# MBO.net
KiCad netlist of a schematic drawn in EAGLE
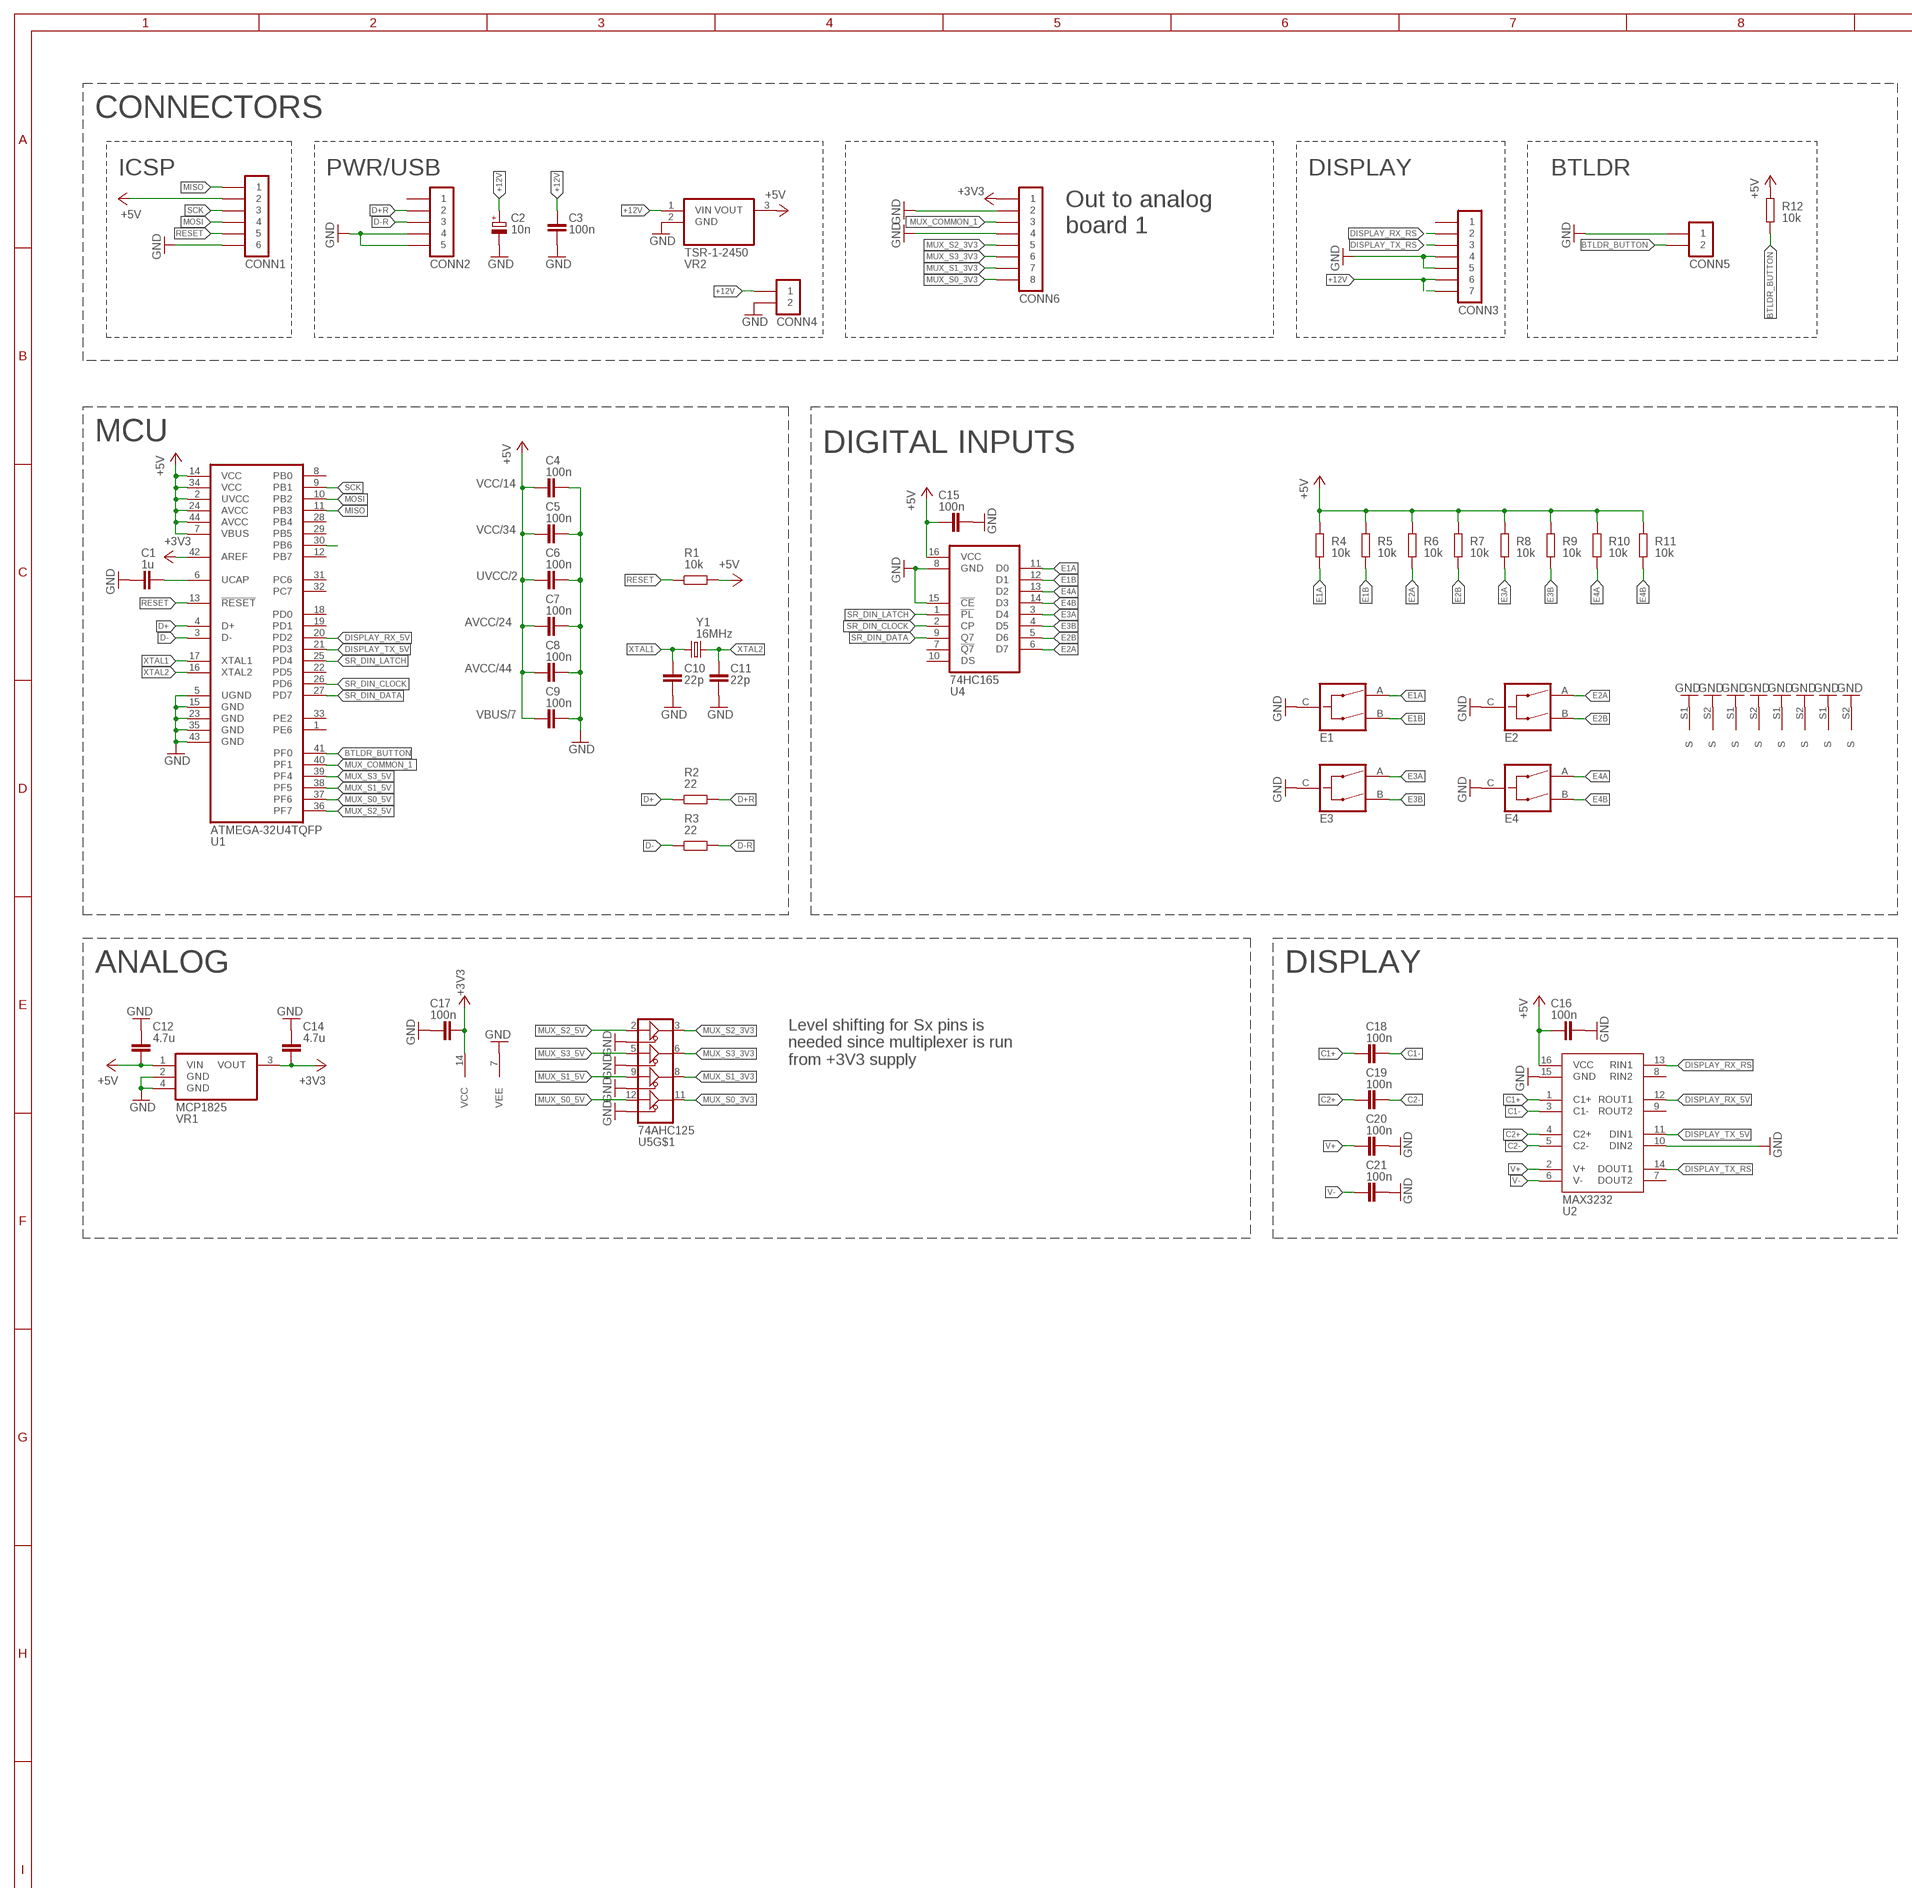
[diagram p0: schematic, sheet 1, part 1 of 2]
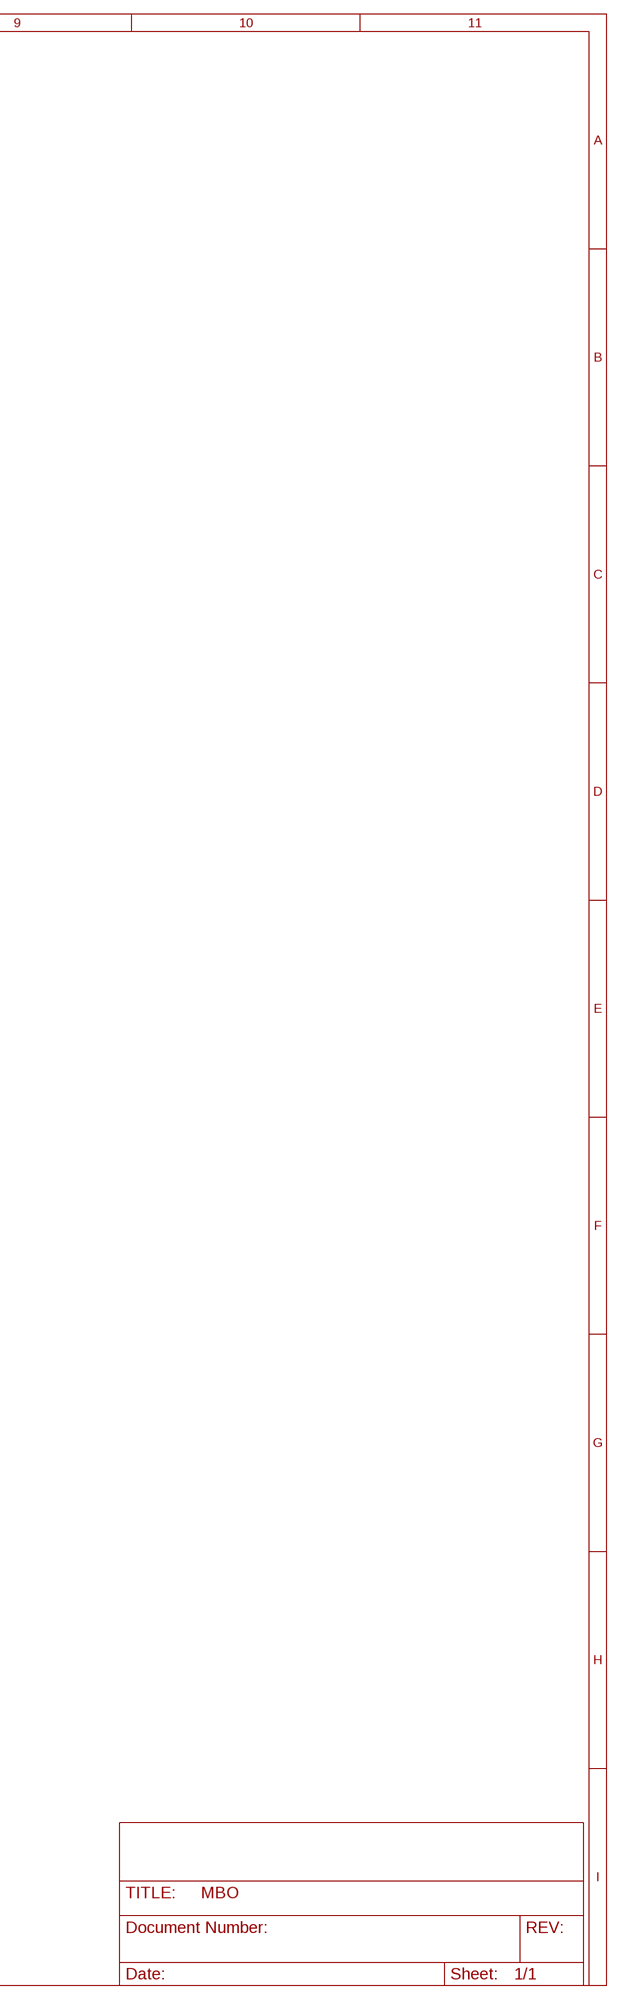
[diagram p1: schematic, sheet 1, part 2 of 2]

(export (version "E")
  (design (tool "Eeschema 10.0.6"))
  (components
    (comp (ref "C1")
      (value "1u")
      (footprint "eagle-import:C0805")
      (libsource (lib "eagle-import") (part "CAPACITOR-0805"))
    )
    (comp (ref "C2")
      (value "10n")
      (footprint "eagle-import:153CLV-0405")
      (fields (field (name "MANUFACTURER") "Multicomp") (field (name "MPN") "MCVVT016M100CA1L"))
      (libsource (lib "eagle-import") (part "ELECTROLYTIC_CAPACITOR-CLV-040516V"))
    )
    (comp (ref "C3")
      (value "100n")
      (footprint "eagle-import:C0805")
      (libsource (lib "eagle-import") (part "CAPACITOR-0805"))
    )
    (comp (ref "C4")
      (value "100n")
      (footprint "eagle-import:C0805")
      (libsource (lib "eagle-import") (part "CAPACITOR-0805"))
    )
    (comp (ref "C5")
      (value "100n")
      (footprint "eagle-import:C0805")
      (libsource (lib "eagle-import") (part "CAPACITOR-0805"))
    )
    (comp (ref "C6")
      (value "100n")
      (footprint "eagle-import:C0805")
      (libsource (lib "eagle-import") (part "CAPACITOR-0805"))
    )
    (comp (ref "C7")
      (value "100n")
      (footprint "eagle-import:C0805")
      (libsource (lib "eagle-import") (part "CAPACITOR-0805"))
    )
    (comp (ref "C8")
      (value "100n")
      (footprint "eagle-import:C0805")
      (libsource (lib "eagle-import") (part "CAPACITOR-0805"))
    )
    (comp (ref "C9")
      (value "100n")
      (footprint "eagle-import:C0805")
      (libsource (lib "eagle-import") (part "CAPACITOR-0805"))
    )
    (comp (ref "C10")
      (value "22p")
      (footprint "eagle-import:C0805")
      (libsource (lib "eagle-import") (part "CAPACITOR-0805"))
    )
    (comp (ref "C11")
      (value "22p")
      (footprint "eagle-import:C0805")
      (libsource (lib "eagle-import") (part "CAPACITOR-0805"))
    )
    (comp (ref "C12")
      (value "4.7u")
      (footprint "eagle-import:C0805")
      (libsource (lib "eagle-import") (part "CAPACITOR-0805"))
    )
    (comp (ref "C14")
      (value "4.7u")
      (footprint "eagle-import:C0805")
      (libsource (lib "eagle-import") (part "CAPACITOR-0805"))
    )
    (comp (ref "C15")
      (value "100n")
      (footprint "eagle-import:C0805")
      (libsource (lib "eagle-import") (part "CAPACITOR-0805"))
    )
    (comp (ref "C16")
      (value "100n")
      (footprint "eagle-import:C0805")
      (libsource (lib "eagle-import") (part "CAPACITOR-0805"))
    )
    (comp (ref "C17")
      (value "100n")
      (footprint "eagle-import:C0805")
      (libsource (lib "eagle-import") (part "CAPACITOR-0805"))
    )
    (comp (ref "C18")
      (value "100n")
      (footprint "eagle-import:C0805")
      (libsource (lib "eagle-import") (part "CAPACITOR-0805"))
    )
    (comp (ref "C19")
      (value "100n")
      (footprint "eagle-import:C0805")
      (libsource (lib "eagle-import") (part "CAPACITOR-0805"))
    )
    (comp (ref "C20")
      (value "100n")
      (footprint "eagle-import:C0805")
      (libsource (lib "eagle-import") (part "CAPACITOR-0805"))
    )
    (comp (ref "C21")
      (value "100n")
      (footprint "eagle-import:C0805")
      (libsource (lib "eagle-import") (part "CAPACITOR-0805"))
    )
    (comp (ref "CONN1")
      (value "PINHD-2X03-TH-2.54MM-V")
      (footprint "eagle-import:2X03-2.54-V")
      (libsource (lib "eagle-import") (part "PINHD-2X03-TH-2.54MM-V"))
    )
    (comp (ref "CONN2")
      (value "PINHD-1X05-JST-XH-H")
      (footprint "eagle-import:JST-XH-05P-H")
      (libsource (lib "eagle-import") (part "PINHD-1X05-JST-XH-H"))
    )
    (comp (ref "CONN3")
      (value "PINHD-1X07-JST-H")
      (footprint "eagle-import:JST-XH-07P-H")
      (libsource (lib "eagle-import") (part "PINHD-1X07-JST-H"))
    )
    (comp (ref "CONN4")
      (value "PINHD-1X02-MOLEX-39357-0002")
      (footprint "eagle-import:MOLEX-39357-0002")
      (fields (field (name "MANUFACTURER") "Molex") (field (name "MPN") "39357-0002"))
      (libsource (lib "eagle-import") (part "PINHD-1X02-MOLEX-39357-0002"))
    )
    (comp (ref "CONN5")
      (value "PINHD-1X02-JST-XH-H")
      (footprint "eagle-import:JST-XH-02P-H")
      (libsource (lib "eagle-import") (part "PINHD-1X02-JST-XH-H"))
    )
    (comp (ref "CONN6")
      (value "PINHD-2X04-IDC-2.54-V")
      (footprint "eagle-import:IDC-08P-2.54")
      (libsource (lib "eagle-import") (part "PINHD-2X04-IDC-2.54-V"))
    )
    (comp (ref "E1")
      (value "ALPS-EC12E24404AX")
      (footprint "eagle-import:EC12E-1")
      (libsource (lib "eagle-import") (part "ALPS-EC12E24404AX"))
    )
    (comp (ref "E2")
      (value "ALPS-EC12E24404AX")
      (footprint "eagle-import:EC12E-1")
      (libsource (lib "eagle-import") (part "ALPS-EC12E24404AX"))
    )
    (comp (ref "E3")
      (value "ALPS-EC12E24404AX")
      (footprint "eagle-import:EC12E-1")
      (libsource (lib "eagle-import") (part "ALPS-EC12E24404AX"))
    )
    (comp (ref "E4")
      (value "ALPS-EC12E24404AX")
      (footprint "eagle-import:EC12E-1")
      (libsource (lib "eagle-import") (part "ALPS-EC12E24404AX"))
    )
    (comp (ref "R1")
      (value "10k")
      (footprint "eagle-import:R0805")
      (libsource (lib "eagle-import") (part "RESISTOR-0805"))
    )
    (comp (ref "R2")
      (value "22")
      (footprint "eagle-import:R0805")
      (libsource (lib "eagle-import") (part "RESISTOR-0805"))
    )
    (comp (ref "R3")
      (value "22")
      (footprint "eagle-import:R0805")
      (libsource (lib "eagle-import") (part "RESISTOR-0805"))
    )
    (comp (ref "R4")
      (value "10k")
      (footprint "eagle-import:R0805")
      (libsource (lib "eagle-import") (part "RESISTOR-0805"))
    )
    (comp (ref "R5")
      (value "10k")
      (footprint "eagle-import:R0805")
      (libsource (lib "eagle-import") (part "RESISTOR-0805"))
    )
    (comp (ref "R6")
      (value "10k")
      (footprint "eagle-import:R0805")
      (libsource (lib "eagle-import") (part "RESISTOR-0805"))
    )
    (comp (ref "R7")
      (value "10k")
      (footprint "eagle-import:R0805")
      (libsource (lib "eagle-import") (part "RESISTOR-0805"))
    )
    (comp (ref "R8")
      (value "10k")
      (footprint "eagle-import:R0805")
      (libsource (lib "eagle-import") (part "RESISTOR-0805"))
    )
    (comp (ref "R9")
      (value "10k")
      (footprint "eagle-import:R0805")
      (libsource (lib "eagle-import") (part "RESISTOR-0805"))
    )
    (comp (ref "R10")
      (value "10k")
      (footprint "eagle-import:R0805")
      (libsource (lib "eagle-import") (part "RESISTOR-0805"))
    )
    (comp (ref "R11")
      (value "10k")
      (footprint "eagle-import:R0805")
      (libsource (lib "eagle-import") (part "RESISTOR-0805"))
    )
    (comp (ref "R12")
      (value "10k")
      (footprint "eagle-import:R0805")
      (libsource (lib "eagle-import") (part "RESISTOR-0805"))
    )
    (comp (ref "U1")
      (value "ATMEGA-32U4TQFP")
      (footprint "eagle-import:TQFP-44")
      (fields (field (name "MPN") "ATMEGA32U4-AUR"))
      (libsource (lib "eagle-import") (part "ATMEGA-32U4TQFP"))
    )
    (comp (ref "U2")
      (value "MAX3232")
      (footprint "eagle-import:SO16")
      (fields (field (name "MANUFACTURER") "Texas Instruments") (field (name "MPN") "MAX3232CDR"))
      (libsource (lib "eagle-import") (part "MAX3232"))
    )
    (comp (ref "U4")
      (value "74HC165")
      (footprint "eagle-import:SO16")
      (fields (field (name "MANUFACTURER") "Nexperia") (field (name "MPN") "74HC165D"))
      (libsource (lib "eagle-import") (part "74165HC"))
    )
    (comp (ref "U5")
      (value "74AHC125")
      (footprint "eagle-import:SOIC14")
      (fields (field (name "MANUFACTURER") "Texas Instruments") (field (name "MPN") "SN74AHC125DR"))
      (libsource (lib "eagle-import") (part "74AHC125"))
    )
    (comp (ref "VR1")
      (value "MCP1825")
      (footprint "eagle-import:SOT223")
      (fields (field (name "MANUFACTURER") "Microchip") (field (name "MPN") "MCP1825S-3302E/DB"))
      (libsource (lib "eagle-import") (part "MCP1825"))
    )
    (comp (ref "VR2")
      (value "TSR-1-2450")
      (footprint "eagle-import:TSR-1-2450")
      (fields (field (name "MANUFACTURER") "Traco Power") (field (name "MPN") "TSR 1-2450"))
      (libsource (lib "eagle-import") (part "TSR-1-2450"))
    )
    (comp (ref "Y1")
      (value "16MHz")
      (footprint "eagle-import:HC49US")
      (fields (field (name "MANUFACTURER") "TXC") (field (name "MPN") "9B-8.000MEEJ-B"))
      (libsource (lib "eagle-import") (part "CRYSTAL-HC49"))
    )
  )
  (nets
    (net (code "1") (name "+3V3") (class "Default")
      (node (ref "C14") (pin "1") (pinfunction "1_1") (pintype "passive"))
      (node (ref "C17") (pin "1") (pinfunction "1_1") (pintype "passive"))
      (node (ref "CONN6") (pin "1") (pinfunction "1_1") (pintype "passive"))
      (node (ref "U1") (pin "42") (pinfunction "AREF_42") (pintype "passive"))
      (node (ref "U5") (pin "14") (pinfunction "VCC_14") (pintype "passive"))
      (node (ref "VR1") (pin "3") (pinfunction "VOUT_3") (pintype "passive"))
    )
    (net (code "2") (name "+5V") (class "Default")
      (node (ref "C12") (pin "1") (pinfunction "1_1") (pintype "passive"))
      (node (ref "C15") (pin "2") (pinfunction "2_2") (pintype "passive"))
      (node (ref "C16") (pin "2") (pinfunction "2_2") (pintype "passive"))
      (node (ref "C4") (pin "1") (pinfunction "1_1") (pintype "passive"))
      (node (ref "C5") (pin "1") (pinfunction "1_1") (pintype "passive"))
      (node (ref "C6") (pin "1") (pinfunction "1_1") (pintype "passive"))
      (node (ref "C7") (pin "1") (pinfunction "1_1") (pintype "passive"))
      (node (ref "C8") (pin "1") (pinfunction "1_1") (pintype "passive"))
      (node (ref "C9") (pin "1") (pinfunction "1_1") (pintype "passive"))
      (node (ref "CONN1") (pin "2") (pinfunction "2_2") (pintype "passive"))
      (node (ref "R1") (pin "2") (pinfunction "2_2") (pintype "passive"))
      (node (ref "R10") (pin "2") (pinfunction "2_2") (pintype "passive"))
      (node (ref "R11") (pin "2") (pinfunction "2_2") (pintype "passive"))
      (node (ref "R12") (pin "2") (pinfunction "2_2") (pintype "passive"))
      (node (ref "R4") (pin "2") (pinfunction "2_2") (pintype "passive"))
      (node (ref "R5") (pin "2") (pinfunction "2_2") (pintype "passive"))
      (node (ref "R6") (pin "2") (pinfunction "2_2") (pintype "passive"))
      (node (ref "R7") (pin "2") (pinfunction "2_2") (pintype "passive"))
      (node (ref "R8") (pin "2") (pinfunction "2_2") (pintype "passive"))
      (node (ref "R9") (pin "2") (pinfunction "2_2") (pintype "passive"))
      (node (ref "U1") (pin "14") (pinfunction "VCC_14") (pintype "passive"))
      (node (ref "U1") (pin "2") (pinfunction "UVCC_2") (pintype "passive"))
      (node (ref "U1") (pin "24") (pinfunction "AVCC_24") (pintype "passive"))
      (node (ref "U1") (pin "34") (pinfunction "VCC_34") (pintype "passive"))
      (node (ref "U1") (pin "44") (pinfunction "AVCC_44") (pintype "passive"))
      (node (ref "U1") (pin "7") (pinfunction "VBUS_7") (pintype "passive"))
      (node (ref "U2") (pin "16") (pinfunction "VCC_16") (pintype "passive"))
      (node (ref "U4") (pin "16") (pinfunction "VCC_16") (pintype "power_in"))
      (node (ref "VR1") (pin "1") (pinfunction "VIN_1") (pintype "passive"))
      (node (ref "VR2") (pin "3") (pinfunction "VOUT_3") (pintype "passive"))
    )
    (net (code "3") (name "+12V") (class "Default")
      (node (ref "C2") (pin "+") (pinfunction "+_+") (pintype "passive"))
      (node (ref "C3") (pin "1") (pinfunction "1_1") (pintype "passive"))
      (node (ref "CONN3") (pin "6") (pinfunction "6_6") (pintype "passive"))
      (node (ref "CONN3") (pin "7") (pinfunction "7_7") (pintype "passive"))
      (node (ref "CONN4") (pin "P$1") (pinfunction "1_P$1") (pintype "passive"))
      (node (ref "VR2") (pin "1") (pinfunction "VIN_1") (pintype "passive"))
    )
    (net (code "4") (name "BTLDR_BUTTON") (class "Default")
      (node (ref "CONN5") (pin "2") (pinfunction "2_2") (pintype "passive"))
      (node (ref "R12") (pin "1") (pinfunction "1_1") (pintype "passive"))
      (node (ref "U1") (pin "41") (pinfunction "PF0_41") (pintype "bidirectional"))
    )
    (net (code "5") (name "C1+") (class "Default")
      (node (ref "C18") (pin "1") (pinfunction "1_1") (pintype "passive"))
      (node (ref "U2") (pin "1") (pinfunction "C1+_1") (pintype "passive"))
    )
    (net (code "6") (name "C1-") (class "Default")
      (node (ref "C18") (pin "2") (pinfunction "2_2") (pintype "passive"))
      (node (ref "U2") (pin "3") (pinfunction "C1-_3") (pintype "passive"))
    )
    (net (code "7") (name "C2+") (class "Default")
      (node (ref "C19") (pin "1") (pinfunction "1_1") (pintype "passive"))
      (node (ref "U2") (pin "4") (pinfunction "C2+_4") (pintype "passive"))
    )
    (net (code "8") (name "C2-") (class "Default")
      (node (ref "C19") (pin "2") (pinfunction "2_2") (pintype "passive"))
      (node (ref "U2") (pin "5") (pinfunction "C2-_5") (pintype "passive"))
    )
    (net (code "9") (name "D+") (class "Default")
      (node (ref "R2") (pin "1") (pinfunction "1_1") (pintype "passive"))
      (node (ref "U1") (pin "4") (pinfunction "D+_4") (pintype "bidirectional"))
    )
    (net (code "10") (name "D+R") (class "Default")
      (node (ref "CONN2") (pin "2") (pinfunction "2_2") (pintype "passive"))
      (node (ref "R2") (pin "2") (pinfunction "2_2") (pintype "passive"))
    )
    (net (code "11") (name "D-") (class "Default")
      (node (ref "R3") (pin "1") (pinfunction "1_1") (pintype "passive"))
      (node (ref "U1") (pin "3") (pinfunction "D-_3") (pintype "bidirectional"))
    )
    (net (code "12") (name "D-R") (class "Default")
      (node (ref "CONN2") (pin "3") (pinfunction "3_3") (pintype "passive"))
      (node (ref "R3") (pin "2") (pinfunction "2_2") (pintype "passive"))
    )
    (net (code "13") (name "DISPLAY_RX_5V") (class "Default")
      (node (ref "U1") (pin "20") (pinfunction "PD2_20") (pintype "bidirectional"))
      (node (ref "U2") (pin "12") (pinfunction "ROUT1_12") (pintype "output"))
    )
    (net (code "14") (name "DISPLAY_RX_RS") (class "Default")
      (node (ref "CONN3") (pin "2") (pinfunction "2_2") (pintype "passive"))
      (node (ref "U2") (pin "13") (pinfunction "RIN1_13") (pintype "input"))
    )
    (net (code "15") (name "DISPLAY_TX_5V") (class "Default")
      (node (ref "U1") (pin "21") (pinfunction "PD3_21") (pintype "bidirectional"))
      (node (ref "U2") (pin "11") (pinfunction "DIN1_11") (pintype "input"))
    )
    (net (code "16") (name "DISPLAY_TX_RS") (class "Default")
      (node (ref "CONN3") (pin "3") (pinfunction "3_3") (pintype "passive"))
      (node (ref "U2") (pin "14") (pinfunction "DOUT1_14") (pintype "output"))
    )
    (net (code "17") (name "E1A") (class "Default")
      (node (ref "E1") (pin "A") (pinfunction "A_A") (pintype "output"))
      (node (ref "R4") (pin "1") (pinfunction "1_1") (pintype "passive"))
      (node (ref "U4") (pin "11") (pinfunction "D0_11") (pintype "input"))
    )
    (net (code "18") (name "E1B") (class "Default")
      (node (ref "E1") (pin "B") (pinfunction "B_B") (pintype "output"))
      (node (ref "R5") (pin "1") (pinfunction "1_1") (pintype "passive"))
      (node (ref "U4") (pin "12") (pinfunction "D1_12") (pintype "input"))
    )
    (net (code "19") (name "E2A") (class "Default")
      (node (ref "E2") (pin "A") (pinfunction "A_A") (pintype "output"))
      (node (ref "R6") (pin "1") (pinfunction "1_1") (pintype "passive"))
      (node (ref "U4") (pin "6") (pinfunction "D7_6") (pintype "input"))
    )
    (net (code "20") (name "E2B") (class "Default")
      (node (ref "E2") (pin "B") (pinfunction "B_B") (pintype "output"))
      (node (ref "R7") (pin "1") (pinfunction "1_1") (pintype "passive"))
      (node (ref "U4") (pin "5") (pinfunction "D6_5") (pintype "input"))
    )
    (net (code "21") (name "E3A") (class "Default")
      (node (ref "E3") (pin "A") (pinfunction "A_A") (pintype "output"))
      (node (ref "R8") (pin "1") (pinfunction "1_1") (pintype "passive"))
      (node (ref "U4") (pin "3") (pinfunction "D4_3") (pintype "input"))
    )
    (net (code "22") (name "E3B") (class "Default")
      (node (ref "E3") (pin "B") (pinfunction "B_B") (pintype "output"))
      (node (ref "R9") (pin "1") (pinfunction "1_1") (pintype "passive"))
      (node (ref "U4") (pin "4") (pinfunction "D5_4") (pintype "input"))
    )
    (net (code "23") (name "E4A") (class "Default")
      (node (ref "E4") (pin "A") (pinfunction "A_A") (pintype "output"))
      (node (ref "R10") (pin "1") (pinfunction "1_1") (pintype "passive"))
      (node (ref "U4") (pin "13") (pinfunction "D2_13") (pintype "input"))
    )
    (net (code "24") (name "E4B") (class "Default")
      (node (ref "E4") (pin "B") (pinfunction "B_B") (pintype "output"))
      (node (ref "R11") (pin "1") (pinfunction "1_1") (pintype "passive"))
      (node (ref "U4") (pin "14") (pinfunction "D3_14") (pintype "input"))
    )
    (net (code "25") (name "GND") (class "Default")
      (node (ref "C1") (pin "2") (pinfunction "2_2") (pintype "passive"))
      (node (ref "C10") (pin "1") (pinfunction "1_1") (pintype "passive"))
      (node (ref "C11") (pin "1") (pinfunction "1_1") (pintype "passive"))
      (node (ref "C12") (pin "2") (pinfunction "2_2") (pintype "passive"))
      (node (ref "C14") (pin "2") (pinfunction "2_2") (pintype "passive"))
      (node (ref "C15") (pin "1") (pinfunction "1_1") (pintype "passive"))
      (node (ref "C16") (pin "1") (pinfunction "1_1") (pintype "passive"))
      (node (ref "C17") (pin "2") (pinfunction "2_2") (pintype "passive"))
      (node (ref "C2") (pin "-") (pinfunction "-_-") (pintype "passive"))
      (node (ref "C20") (pin "2") (pinfunction "2_2") (pintype "passive"))
      (node (ref "C21") (pin "2") (pinfunction "2_2") (pintype "passive"))
      (node (ref "C3") (pin "2") (pinfunction "2_2") (pintype "passive"))
      (node (ref "C4") (pin "2") (pinfunction "2_2") (pintype "passive"))
      (node (ref "C5") (pin "2") (pinfunction "2_2") (pintype "passive"))
      (node (ref "C6") (pin "2") (pinfunction "2_2") (pintype "passive"))
      (node (ref "C7") (pin "2") (pinfunction "2_2") (pintype "passive"))
      (node (ref "C8") (pin "2") (pinfunction "2_2") (pintype "passive"))
      (node (ref "C9") (pin "2") (pinfunction "2_2") (pintype "passive"))
      (node (ref "CONN1") (pin "6") (pinfunction "6_6") (pintype "passive"))
      (node (ref "CONN2") (pin "4") (pinfunction "4_4") (pintype "passive"))
      (node (ref "CONN2") (pin "5") (pinfunction "5_5") (pintype "passive"))
      (node (ref "CONN3") (pin "4") (pinfunction "4_4") (pintype "passive"))
      (node (ref "CONN3") (pin "5") (pinfunction "5_5") (pintype "passive"))
      (node (ref "CONN4") (pin "P$2") (pinfunction "2_P$2") (pintype "passive"))
      (node (ref "CONN5") (pin "1") (pinfunction "1_1") (pintype "passive"))
      (node (ref "CONN6") (pin "2") (pinfunction "2_2") (pintype "passive"))
      (node (ref "CONN6") (pin "4") (pinfunction "4_4") (pintype "passive"))
      (node (ref "E1") (pin "C") (pinfunction "C_C") (pintype "input"))
      (node (ref "E1") (pin "S1") (pinfunction "S_S1") (pintype "passive"))
      (node (ref "E1") (pin "S2") (pinfunction "S_S2") (pintype "passive"))
      (node (ref "E2") (pin "C") (pinfunction "C_C") (pintype "input"))
      (node (ref "E2") (pin "S1") (pinfunction "S_S1") (pintype "passive"))
      (node (ref "E2") (pin "S2") (pinfunction "S_S2") (pintype "passive"))
      (node (ref "E3") (pin "C") (pinfunction "C_C") (pintype "input"))
      (node (ref "E3") (pin "S1") (pinfunction "S_S1") (pintype "passive"))
      (node (ref "E3") (pin "S2") (pinfunction "S_S2") (pintype "passive"))
      (node (ref "E4") (pin "C") (pinfunction "C_C") (pintype "input"))
      (node (ref "E4") (pin "S1") (pinfunction "S_S1") (pintype "passive"))
      (node (ref "E4") (pin "S2") (pinfunction "S_S2") (pintype "passive"))
      (node (ref "U1") (pin "15") (pinfunction "GND_15") (pintype "passive"))
      (node (ref "U1") (pin "23") (pinfunction "GND_23") (pintype "passive"))
      (node (ref "U1") (pin "35") (pinfunction "GND_35") (pintype "passive"))
      (node (ref "U1") (pin "43") (pinfunction "GND_43") (pintype "passive"))
      (node (ref "U1") (pin "5") (pinfunction "UGND_5") (pintype "passive"))
      (node (ref "U2") (pin "10") (pinfunction "DIN2_10") (pintype "input"))
      (node (ref "U2") (pin "15") (pinfunction "GND_15") (pintype "passive"))
      (node (ref "U4") (pin "15") (pinfunction "~{CE}_15") (pintype "input"))
      (node (ref "U4") (pin "8") (pinfunction "GND_8") (pintype "power_in"))
      (node (ref "U5") (pin "1") (pinfunction "1~{(OE})_1") (pintype "bidirectional"))
      (node (ref "U5") (pin "10") (pinfunction "3~{(OE})_10") (pintype "bidirectional"))
      (node (ref "U5") (pin "13") (pinfunction "4~{(OE})_13") (pintype "bidirectional"))
      (node (ref "U5") (pin "4") (pinfunction "2~{(OE})_4") (pintype "bidirectional"))
      (node (ref "U5") (pin "7") (pinfunction "VEE_7") (pintype "passive"))
      (node (ref "VR1") (pin "2") (pinfunction "GND_2") (pintype "passive"))
      (node (ref "VR1") (pin "4") (pinfunction "GND_4") (pintype "passive"))
      (node (ref "VR2") (pin "2") (pinfunction "GND_2") (pintype "passive"))
    )
    (net (code "26") (name "MISO") (class "Default")
      (node (ref "CONN1") (pin "1") (pinfunction "1_1") (pintype "passive"))
      (node (ref "U1") (pin "11") (pinfunction "PB3_11") (pintype "bidirectional"))
    )
    (net (code "27") (name "MOSI") (class "Default")
      (node (ref "CONN1") (pin "4") (pinfunction "4_4") (pintype "passive"))
      (node (ref "U1") (pin "10") (pinfunction "PB2_10") (pintype "bidirectional"))
    )
    (net (code "28") (name "MUX_COMMON_1") (class "Default")
      (node (ref "CONN6") (pin "3") (pinfunction "3_3") (pintype "passive"))
      (node (ref "U1") (pin "40") (pinfunction "PF1_40") (pintype "bidirectional"))
    )
    (net (code "29") (name "MUX_S0_3V3") (class "Default")
      (node (ref "CONN6") (pin "8") (pinfunction "8_8") (pintype "passive"))
      (node (ref "U5") (pin "11") (pinfunction "4Y_11") (pintype "bidirectional"))
    )
    (net (code "30") (name "MUX_S0_5V") (class "Default")
      (node (ref "U1") (pin "37") (pinfunction "PF6_37") (pintype "bidirectional"))
      (node (ref "U5") (pin "12") (pinfunction "4A_12") (pintype "bidirectional"))
    )
    (net (code "31") (name "MUX_S1_3V3") (class "Default")
      (node (ref "CONN6") (pin "7") (pinfunction "7_7") (pintype "passive"))
      (node (ref "U5") (pin "8") (pinfunction "3Y_8") (pintype "bidirectional"))
    )
    (net (code "32") (name "MUX_S1_5V") (class "Default")
      (node (ref "U1") (pin "38") (pinfunction "PF5_38") (pintype "bidirectional"))
      (node (ref "U5") (pin "9") (pinfunction "3A_9") (pintype "bidirectional"))
    )
    (net (code "33") (name "MUX_S2_3V3") (class "Default")
      (node (ref "CONN6") (pin "5") (pinfunction "5_5") (pintype "passive"))
      (node (ref "U5") (pin "3") (pinfunction "1Y_3") (pintype "bidirectional"))
    )
    (net (code "34") (name "MUX_S2_5V") (class "Default")
      (node (ref "U1") (pin "36") (pinfunction "PF7_36") (pintype "bidirectional"))
      (node (ref "U5") (pin "2") (pinfunction "1A_2") (pintype "bidirectional"))
    )
    (net (code "35") (name "MUX_S3_3V3") (class "Default")
      (node (ref "CONN6") (pin "6") (pinfunction "6_6") (pintype "passive"))
      (node (ref "U5") (pin "6") (pinfunction "2Y_6") (pintype "bidirectional"))
    )
    (net (code "36") (name "MUX_S3_5V") (class "Default")
      (node (ref "U1") (pin "39") (pinfunction "PF4_39") (pintype "bidirectional"))
      (node (ref "U5") (pin "5") (pinfunction "2A_5") (pintype "bidirectional"))
    )
    (net (code "37") (name "Net-(U1-UCAP)") (class "Default")
      (node (ref "C1") (pin "1") (pinfunction "1_1") (pintype "passive"))
      (node (ref "U1") (pin "6") (pinfunction "UCAP_6") (pintype "passive"))
    )
    (net (code "38") (name "RESET") (class "Default")
      (node (ref "CONN1") (pin "5") (pinfunction "5_5") (pintype "passive"))
      (node (ref "R1") (pin "1") (pinfunction "1_1") (pintype "passive"))
      (node (ref "U1") (pin "13") (pinfunction "~{RESET}_13") (pintype "input"))
    )
    (net (code "39") (name "SCK") (class "Default")
      (node (ref "CONN1") (pin "3") (pinfunction "3_3") (pintype "passive"))
      (node (ref "U1") (pin "9") (pinfunction "PB1_9") (pintype "bidirectional"))
    )
    (net (code "40") (name "SR_DIN_CLOCK") (class "Default")
      (node (ref "U1") (pin "26") (pinfunction "PD6_26") (pintype "bidirectional"))
      (node (ref "U4") (pin "2") (pinfunction "CP_2") (pintype "bidirectional"))
    )
    (net (code "41") (name "SR_DIN_DATA") (class "Default")
      (node (ref "U1") (pin "27") (pinfunction "PD7_27") (pintype "bidirectional"))
      (node (ref "U4") (pin "9") (pinfunction "Q7_9") (pintype "output"))
    )
    (net (code "42") (name "SR_DIN_LATCH") (class "Default")
      (node (ref "U1") (pin "25") (pinfunction "PD4_25") (pintype "bidirectional"))
      (node (ref "U4") (pin "1") (pinfunction "~{PL}_1") (pintype "input"))
    )
    (net (code "43") (name "V+") (class "Default")
      (node (ref "C20") (pin "1") (pinfunction "1_1") (pintype "passive"))
      (node (ref "U2") (pin "2") (pinfunction "V+_2") (pintype "output"))
    )
    (net (code "44") (name "V-") (class "Default")
      (node (ref "C21") (pin "1") (pinfunction "1_1") (pintype "passive"))
      (node (ref "U2") (pin "6") (pinfunction "V-_6") (pintype "output"))
    )
    (net (code "45") (name "XTAL1") (class "Default")
      (node (ref "C10") (pin "2") (pinfunction "2_2") (pintype "passive"))
      (node (ref "U1") (pin "17") (pinfunction "XTAL1_17") (pintype "bidirectional"))
      (node (ref "Y1") (pin "1") (pinfunction "1_1") (pintype "passive"))
    )
    (net (code "46") (name "XTAL2") (class "Default")
      (node (ref "C11") (pin "2") (pinfunction "2_2") (pintype "passive"))
      (node (ref "U1") (pin "16") (pinfunction "XTAL2_16") (pintype "bidirectional"))
      (node (ref "Y1") (pin "2") (pinfunction "2_2") (pintype "passive"))
    )
    (net (code "47") (name "unconnected-(CONN2-Pad1)") (class "Default")
      (node (ref "CONN2") (pin "1") (pinfunction "1_1") (pintype "passive"))
    )
    (net (code "48") (name "unconnected-(CONN3-Pad1)") (class "Default")
      (node (ref "CONN3") (pin "1") (pinfunction "1_1") (pintype "passive"))
    )
    (net (code "49") (name "unconnected-(U1-PB0-Pad8)") (class "Default")
      (node (ref "U1") (pin "8") (pinfunction "PB0_8") (pintype "bidirectional"))
    )
    (net (code "50") (name "unconnected-(U1-PB4-Pad28)") (class "Default")
      (node (ref "U1") (pin "28") (pinfunction "PB4_28") (pintype "bidirectional"))
    )
    (net (code "51") (name "unconnected-(U1-PB5-Pad29)") (class "Default")
      (node (ref "U1") (pin "29") (pinfunction "PB5_29") (pintype "bidirectional"))
    )
    (net (code "52") (name "unconnected-(U1-PB6-Pad30)") (class "Default")
      (node (ref "U1") (pin "30") (pinfunction "PB6_30") (pintype "bidirectional"))
    )
    (net (code "53") (name "unconnected-(U1-PB7-Pad12)") (class "Default")
      (node (ref "U1") (pin "12") (pinfunction "PB7_12") (pintype "bidirectional"))
    )
    (net (code "54") (name "unconnected-(U1-PC6-Pad31)") (class "Default")
      (node (ref "U1") (pin "31") (pinfunction "PC6_31") (pintype "bidirectional"))
    )
    (net (code "55") (name "unconnected-(U1-PC7-Pad32)") (class "Default")
      (node (ref "U1") (pin "32") (pinfunction "PC7_32") (pintype "bidirectional"))
    )
    (net (code "56") (name "unconnected-(U1-PD0-Pad18)") (class "Default")
      (node (ref "U1") (pin "18") (pinfunction "PD0_18") (pintype "bidirectional"))
    )
    (net (code "57") (name "unconnected-(U1-PD1-Pad19)") (class "Default")
      (node (ref "U1") (pin "19") (pinfunction "PD1_19") (pintype "bidirectional"))
    )
    (net (code "58") (name "unconnected-(U1-PD5-Pad22)") (class "Default")
      (node (ref "U1") (pin "22") (pinfunction "PD5_22") (pintype "bidirectional"))
    )
    (net (code "59") (name "unconnected-(U1-PE2-Pad33)") (class "Default")
      (node (ref "U1") (pin "33") (pinfunction "PE2_33") (pintype "bidirectional"))
    )
    (net (code "60") (name "unconnected-(U1-PE6-Pad1)") (class "Default")
      (node (ref "U1") (pin "1") (pinfunction "PE6_1") (pintype "bidirectional"))
    )
    (net (code "61") (name "unconnected-(U2-DOUT2-Pad7)") (class "Default")
      (node (ref "U2") (pin "7") (pinfunction "DOUT2_7") (pintype "output"))
    )
    (net (code "62") (name "unconnected-(U2-RIN2-Pad8)") (class "Default")
      (node (ref "U2") (pin "8") (pinfunction "RIN2_8") (pintype "input"))
    )
    (net (code "63") (name "unconnected-(U2-ROUT2-Pad9)") (class "Default")
      (node (ref "U2") (pin "9") (pinfunction "ROUT2_9") (pintype "output"))
    )
    (net (code "64") (name "unconnected-(U4-DS-Pad10)") (class "Default")
      (node (ref "U4") (pin "10") (pinfunction "DS_10") (pintype "bidirectional"))
    )
    (net (code "65") (name "unconnected-(U4-~{Q7}-Pad7)") (class "Default")
      (node (ref "U4") (pin "7") (pinfunction "~{Q7}_7") (pintype "output"))
    )
  )
)
